# DigitalStylophone.net
KiCad netlist of a schematic drawn in EAGLE
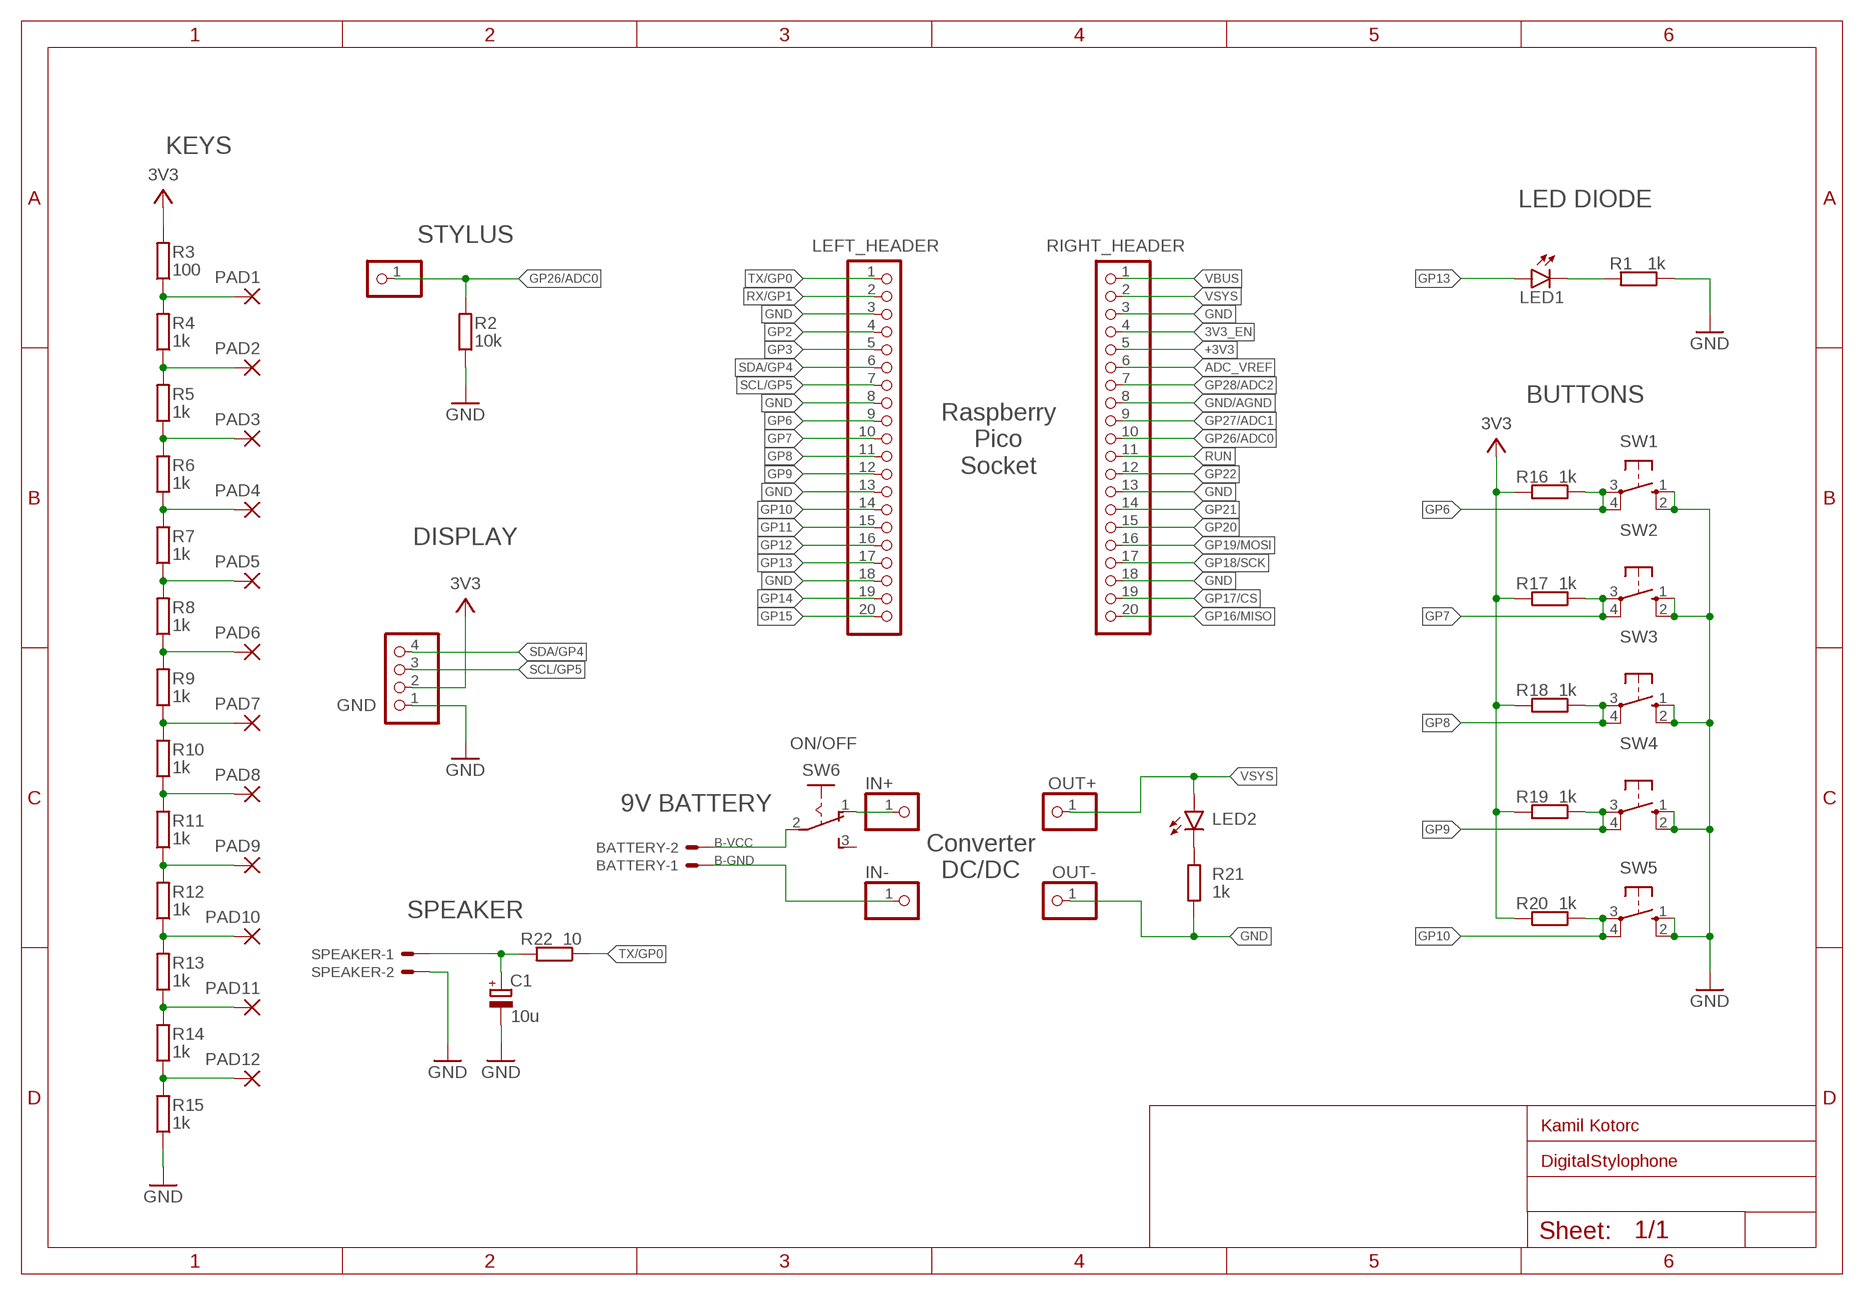
[diagram p0: schematic, sheet 1]

(export (version "E")
  (design (tool "Eeschema 10.0.6"))
  (components
    (comp (ref "BATTERY")
      (value "9V BATTERY")
      (footprint "eagle-import:22-23-2021")
      (fields (field (name "MF") "MOLEX") (field (name "MPN") "22-23-2021"))
      (libsource (lib "eagle-import") (part "22-23-2021"))
    )
    (comp (ref "C1")
      (value "10u")
      (footprint "eagle-import:E2,5-5")
      (libsource (lib "eagle-import") (part "CPOL-EUE2.5-5"))
    )
    (comp (ref "DISPLAY")
      (value "GND")
      (footprint "eagle-import:1X04")
      (libsource (lib "eagle-import") (part "PINHD-1X4"))
    )
    (comp (ref "IN+")
      (value "PINHD-1X1")
      (footprint "eagle-import:1X01")
      (libsource (lib "eagle-import") (part "PINHD-1X1"))
    )
    (comp (ref "IN-")
      (value "PINHD-1X1")
      (footprint "eagle-import:1X01")
      (libsource (lib "eagle-import") (part "PINHD-1X1"))
    )
    (comp (ref "LED1")
      (value "LED5MM")
      (footprint "eagle-import:LED5MM")
      (libsource (lib "eagle-import") (part "LED5MM"))
    )
    (comp (ref "LED2")
      (value "LED3MM")
      (footprint "eagle-import:LED3MM")
      (libsource (lib "eagle-import") (part "LED3MM"))
    )
    (comp (ref "LEFT_HEADER")
      (value "PINHD-1X20")
      (footprint "eagle-import:1X20")
      (libsource (lib "eagle-import") (part "PINHD-1X20"))
    )
    (comp (ref "OUT+")
      (value "PINHD-1X1")
      (footprint "eagle-import:1X01")
      (libsource (lib "eagle-import") (part "PINHD-1X1"))
    )
    (comp (ref "OUT-")
      (value "PINHD-1X1")
      (footprint "eagle-import:1X01")
      (libsource (lib "eagle-import") (part "PINHD-1X1"))
    )
    (comp (ref "PAD1")
      (value "SMD5")
      (footprint "eagle-import:SMD2,54-5,08")
      (libsource (lib "eagle-import") (part "SMD5"))
    )
    (comp (ref "PAD2")
      (value "SMD5")
      (footprint "eagle-import:SMD2,54-5,08")
      (libsource (lib "eagle-import") (part "SMD5"))
    )
    (comp (ref "PAD3")
      (value "SMD5")
      (footprint "eagle-import:SMD2,54-5,08")
      (libsource (lib "eagle-import") (part "SMD5"))
    )
    (comp (ref "PAD4")
      (value "SMD5")
      (footprint "eagle-import:SMD2,54-5,08")
      (libsource (lib "eagle-import") (part "SMD5"))
    )
    (comp (ref "PAD5")
      (value "SMD5")
      (footprint "eagle-import:SMD2,54-5,08")
      (libsource (lib "eagle-import") (part "SMD5"))
    )
    (comp (ref "PAD6")
      (value "SMD5")
      (footprint "eagle-import:SMD2,54-5,08")
      (libsource (lib "eagle-import") (part "SMD5"))
    )
    (comp (ref "PAD7")
      (value "SMD5")
      (footprint "eagle-import:SMD2,54-5,08")
      (libsource (lib "eagle-import") (part "SMD5"))
    )
    (comp (ref "PAD8")
      (value "SMD5")
      (footprint "eagle-import:SMD2,54-5,08")
      (libsource (lib "eagle-import") (part "SMD5"))
    )
    (comp (ref "PAD9")
      (value "SMD5")
      (footprint "eagle-import:SMD2,54-5,08")
      (libsource (lib "eagle-import") (part "SMD5"))
    )
    (comp (ref "PAD10")
      (value "SMD5")
      (footprint "eagle-import:SMD2,54-5,08")
      (libsource (lib "eagle-import") (part "SMD5"))
    )
    (comp (ref "PAD11")
      (value "SMD5")
      (footprint "eagle-import:SMD2,54-5,08")
      (libsource (lib "eagle-import") (part "SMD5"))
    )
    (comp (ref "PAD12")
      (value "SMD5")
      (footprint "eagle-import:SMD2,54-5,08")
      (libsource (lib "eagle-import") (part "SMD5"))
    )
    (comp (ref "R1")
      (value "1k")
      (footprint "eagle-import:0204_7")
      (libsource (lib "eagle-import") (part "R-EU_0204/7"))
    )
    (comp (ref "R2")
      (value "10k")
      (footprint "eagle-import:0204_7")
      (libsource (lib "eagle-import") (part "R-EU_0204/7"))
    )
    (comp (ref "R3")
      (value "100")
      (footprint "eagle-import:0204_7")
      (libsource (lib "eagle-import") (part "R-EU_0204/7"))
    )
    (comp (ref "R4")
      (value "1k")
      (footprint "eagle-import:0204_7")
      (libsource (lib "eagle-import") (part "R-EU_0204/7"))
    )
    (comp (ref "R5")
      (value "1k")
      (footprint "eagle-import:0204_7")
      (libsource (lib "eagle-import") (part "R-EU_0204/7"))
    )
    (comp (ref "R6")
      (value "1k")
      (footprint "eagle-import:0204_7")
      (libsource (lib "eagle-import") (part "R-EU_0204/7"))
    )
    (comp (ref "R7")
      (value "1k")
      (footprint "eagle-import:0204_7")
      (libsource (lib "eagle-import") (part "R-EU_0204/7"))
    )
    (comp (ref "R8")
      (value "1k")
      (footprint "eagle-import:0204_7")
      (libsource (lib "eagle-import") (part "R-EU_0204/7"))
    )
    (comp (ref "R9")
      (value "1k")
      (footprint "eagle-import:0204_7")
      (libsource (lib "eagle-import") (part "R-EU_0204/7"))
    )
    (comp (ref "R10")
      (value "1k")
      (footprint "eagle-import:0204_7")
      (libsource (lib "eagle-import") (part "R-EU_0204/7"))
    )
    (comp (ref "R11")
      (value "1k")
      (footprint "eagle-import:0204_7")
      (libsource (lib "eagle-import") (part "R-EU_0204/7"))
    )
    (comp (ref "R12")
      (value "1k")
      (footprint "eagle-import:0204_7")
      (libsource (lib "eagle-import") (part "R-EU_0204/7"))
    )
    (comp (ref "R13")
      (value "1k")
      (footprint "eagle-import:0204_7")
      (libsource (lib "eagle-import") (part "R-EU_0204/7"))
    )
    (comp (ref "R14")
      (value "1k")
      (footprint "eagle-import:0204_7")
      (libsource (lib "eagle-import") (part "R-EU_0204/7"))
    )
    (comp (ref "R15")
      (value "1k")
      (footprint "eagle-import:0204_7")
      (libsource (lib "eagle-import") (part "R-EU_0204/7"))
    )
    (comp (ref "R16")
      (value "1k")
      (footprint "eagle-import:0204_7")
      (libsource (lib "eagle-import") (part "R-EU_0204/7"))
    )
    (comp (ref "R17")
      (value "1k")
      (footprint "eagle-import:0204_7")
      (libsource (lib "eagle-import") (part "R-EU_0204/7"))
    )
    (comp (ref "R18")
      (value "1k")
      (footprint "eagle-import:0204_7")
      (libsource (lib "eagle-import") (part "R-EU_0204/7"))
    )
    (comp (ref "R19")
      (value "1k")
      (footprint "eagle-import:0204_7")
      (libsource (lib "eagle-import") (part "R-EU_0204/7"))
    )
    (comp (ref "R20")
      (value "1k")
      (footprint "eagle-import:0204_7")
      (libsource (lib "eagle-import") (part "R-EU_0204/7"))
    )
    (comp (ref "R21")
      (value "1k")
      (footprint "eagle-import:0204_7")
      (libsource (lib "eagle-import") (part "R-EU_0204/7"))
    )
    (comp (ref "R22")
      (value "10")
      (footprint "eagle-import:0204_7")
      (libsource (lib "eagle-import") (part "R-EU_0204/7"))
    )
    (comp (ref "RIGHT_HEADER")
      (value "PINHD-1X20")
      (footprint "eagle-import:1X20")
      (libsource (lib "eagle-import") (part "PINHD-1X20"))
    )
    (comp (ref "SPEAKER")
      (value "SPEAKER")
      (footprint "eagle-import:22-23-2021")
      (fields (field (name "MF") "MOLEX") (field (name "MPN") "22-23-2021"))
      (libsource (lib "eagle-import") (part "22-23-2021"))
    )
    (comp (ref "STYLUS")
      (value "PINHD-1X1")
      (footprint "eagle-import:1X01")
      (libsource (lib "eagle-import") (part "PINHD-1X1"))
    )
    (comp (ref "SW1")
      (value "10-XX")
      (footprint "eagle-import:B3F-10XX")
      (fields (field (name "MPN") "B3F-1000"))
      (libsource (lib "eagle-import") (part "10-XX"))
    )
    (comp (ref "SW2")
      (value "10-XX")
      (footprint "eagle-import:B3F-10XX")
      (fields (field (name "MPN") "B3F-1000"))
      (libsource (lib "eagle-import") (part "10-XX"))
    )
    (comp (ref "SW3")
      (value "10-XX")
      (footprint "eagle-import:B3F-10XX")
      (fields (field (name "MPN") "B3F-1000"))
      (libsource (lib "eagle-import") (part "10-XX"))
    )
    (comp (ref "SW4")
      (value "10-XX")
      (footprint "eagle-import:B3F-10XX")
      (fields (field (name "MPN") "B3F-1000"))
      (libsource (lib "eagle-import") (part "10-XX"))
    )
    (comp (ref "SW5")
      (value "10-XX")
      (footprint "eagle-import:B3F-10XX")
      (fields (field (name "MPN") "B3F-1000"))
      (libsource (lib "eagle-import") (part "10-XX"))
    )
    (comp (ref "SW6")
      (value "ON/OFF")
      (footprint "eagle-import:255SB")
      (libsource (lib "eagle-import") (part "255SB"))
    )
  )
  (nets
    (net (code "1") (name "+3V3") (class "Default")
      (node (ref "DISPLAY") (pin "2") (pinfunction "2_2") (pintype "passive"))
      (node (ref "R16") (pin "2") (pinfunction "2_2") (pintype "passive"))
      (node (ref "R17") (pin "2") (pinfunction "2_2") (pintype "passive"))
      (node (ref "R18") (pin "2") (pinfunction "2_2") (pintype "passive"))
      (node (ref "R19") (pin "2") (pinfunction "2_2") (pintype "passive"))
      (node (ref "R20") (pin "2") (pinfunction "2_2") (pintype "passive"))
      (node (ref "R3") (pin "2") (pinfunction "2_2") (pintype "passive"))
      (node (ref "RIGHT_HEADER") (pin "5") (pinfunction "5_5") (pintype "passive"))
    )
    (net (code "2") (name "/B-GND") (class "Default")
      (node (ref "BATTERY") (pin "1") (pinfunction "S_1") (pintype "passive"))
      (node (ref "IN-") (pin "1") (pinfunction "1_1") (pintype "passive"))
    )
    (net (code "3") (name "/B-VCC") (class "Default")
      (node (ref "BATTERY") (pin "2") (pinfunction "S_2") (pintype "passive"))
      (node (ref "SW6") (pin "2") (pinfunction "P_2") (pintype "passive"))
    )
    (net (code "4") (name "3V3_EN") (class "Default")
      (node (ref "RIGHT_HEADER") (pin "4") (pinfunction "4_4") (pintype "passive"))
    )
    (net (code "5") (name "ADC_VREF") (class "Default")
      (node (ref "RIGHT_HEADER") (pin "6") (pinfunction "6_6") (pintype "passive"))
    )
    (net (code "6") (name "GND") (class "Default")
      (node (ref "C1") (pin "-") (pinfunction "-_-") (pintype "passive"))
      (node (ref "DISPLAY") (pin "1") (pinfunction "1_1") (pintype "passive"))
      (node (ref "LEFT_HEADER") (pin "13") (pinfunction "13_13") (pintype "passive"))
      (node (ref "LEFT_HEADER") (pin "18") (pinfunction "18_18") (pintype "passive"))
      (node (ref "LEFT_HEADER") (pin "3") (pinfunction "3_3") (pintype "passive"))
      (node (ref "LEFT_HEADER") (pin "8") (pinfunction "8_8") (pintype "passive"))
      (node (ref "OUT-") (pin "1") (pinfunction "1_1") (pintype "passive"))
      (node (ref "R1") (pin "1") (pinfunction "1_1") (pintype "passive"))
      (node (ref "R15") (pin "1") (pinfunction "1_1") (pintype "passive"))
      (node (ref "R2") (pin "1") (pinfunction "1_1") (pintype "passive"))
      (node (ref "R21") (pin "1") (pinfunction "1_1") (pintype "passive"))
      (node (ref "RIGHT_HEADER") (pin "13") (pinfunction "13_13") (pintype "passive"))
      (node (ref "RIGHT_HEADER") (pin "18") (pinfunction "18_18") (pintype "passive"))
      (node (ref "RIGHT_HEADER") (pin "3") (pinfunction "3_3") (pintype "passive"))
      (node (ref "SPEAKER") (pin "2") (pinfunction "S_2") (pintype "passive"))
      (node (ref "SW1") (pin "1") (pinfunction "S_1") (pintype "passive"))
      (node (ref "SW1") (pin "2") (pinfunction "S1_2") (pintype "passive"))
      (node (ref "SW2") (pin "1") (pinfunction "S_1") (pintype "passive"))
      (node (ref "SW2") (pin "2") (pinfunction "S1_2") (pintype "passive"))
      (node (ref "SW3") (pin "1") (pinfunction "S_1") (pintype "passive"))
      (node (ref "SW3") (pin "2") (pinfunction "S1_2") (pintype "passive"))
      (node (ref "SW4") (pin "1") (pinfunction "S_1") (pintype "passive"))
      (node (ref "SW4") (pin "2") (pinfunction "S1_2") (pintype "passive"))
      (node (ref "SW5") (pin "1") (pinfunction "S_1") (pintype "passive"))
      (node (ref "SW5") (pin "2") (pinfunction "S1_2") (pintype "passive"))
    )
    (net (code "7") (name "GND{slash}AGND") (class "Default")
      (node (ref "RIGHT_HEADER") (pin "8") (pinfunction "8_8") (pintype "passive"))
    )
    (net (code "8") (name "GP2") (class "Default")
      (node (ref "LEFT_HEADER") (pin "4") (pinfunction "4_4") (pintype "passive"))
    )
    (net (code "9") (name "GP3") (class "Default")
      (node (ref "LEFT_HEADER") (pin "5") (pinfunction "5_5") (pintype "passive"))
    )
    (net (code "10") (name "GP6") (class "Default")
      (node (ref "LEFT_HEADER") (pin "9") (pinfunction "9_9") (pintype "passive"))
      (node (ref "R16") (pin "1") (pinfunction "1_1") (pintype "passive"))
      (node (ref "SW1") (pin "3") (pinfunction "P_3") (pintype "passive"))
      (node (ref "SW1") (pin "4") (pinfunction "P1_4") (pintype "passive"))
    )
    (net (code "11") (name "GP7") (class "Default")
      (node (ref "LEFT_HEADER") (pin "10") (pinfunction "10_10") (pintype "passive"))
      (node (ref "R17") (pin "1") (pinfunction "1_1") (pintype "passive"))
      (node (ref "SW2") (pin "3") (pinfunction "P_3") (pintype "passive"))
      (node (ref "SW2") (pin "4") (pinfunction "P1_4") (pintype "passive"))
    )
    (net (code "12") (name "GP8") (class "Default")
      (node (ref "LEFT_HEADER") (pin "11") (pinfunction "11_11") (pintype "passive"))
      (node (ref "R18") (pin "1") (pinfunction "1_1") (pintype "passive"))
      (node (ref "SW3") (pin "3") (pinfunction "P_3") (pintype "passive"))
      (node (ref "SW3") (pin "4") (pinfunction "P1_4") (pintype "passive"))
    )
    (net (code "13") (name "GP9") (class "Default")
      (node (ref "LEFT_HEADER") (pin "12") (pinfunction "12_12") (pintype "passive"))
      (node (ref "R19") (pin "1") (pinfunction "1_1") (pintype "passive"))
      (node (ref "SW4") (pin "3") (pinfunction "P_3") (pintype "passive"))
      (node (ref "SW4") (pin "4") (pinfunction "P1_4") (pintype "passive"))
    )
    (net (code "14") (name "GP10") (class "Default")
      (node (ref "LEFT_HEADER") (pin "14") (pinfunction "14_14") (pintype "passive"))
      (node (ref "R20") (pin "1") (pinfunction "1_1") (pintype "passive"))
      (node (ref "SW5") (pin "3") (pinfunction "P_3") (pintype "passive"))
      (node (ref "SW5") (pin "4") (pinfunction "P1_4") (pintype "passive"))
    )
    (net (code "15") (name "GP11") (class "Default")
      (node (ref "LEFT_HEADER") (pin "15") (pinfunction "15_15") (pintype "passive"))
    )
    (net (code "16") (name "GP12") (class "Default")
      (node (ref "LEFT_HEADER") (pin "16") (pinfunction "16_16") (pintype "passive"))
    )
    (net (code "17") (name "GP13") (class "Default")
      (node (ref "LED1") (pin "A") (pinfunction "A_A") (pintype "passive"))
      (node (ref "LEFT_HEADER") (pin "17") (pinfunction "17_17") (pintype "passive"))
    )
    (net (code "18") (name "GP14") (class "Default")
      (node (ref "LEFT_HEADER") (pin "19") (pinfunction "19_19") (pintype "passive"))
    )
    (net (code "19") (name "GP15") (class "Default")
      (node (ref "LEFT_HEADER") (pin "20") (pinfunction "20_20") (pintype "passive"))
    )
    (net (code "20") (name "GP16{slash}MISO") (class "Default")
      (node (ref "RIGHT_HEADER") (pin "20") (pinfunction "20_20") (pintype "passive"))
    )
    (net (code "21") (name "GP17{slash}CS") (class "Default")
      (node (ref "RIGHT_HEADER") (pin "19") (pinfunction "19_19") (pintype "passive"))
    )
    (net (code "22") (name "GP18{slash}SCK") (class "Default")
      (node (ref "RIGHT_HEADER") (pin "17") (pinfunction "17_17") (pintype "passive"))
    )
    (net (code "23") (name "GP19{slash}MOSI") (class "Default")
      (node (ref "RIGHT_HEADER") (pin "16") (pinfunction "16_16") (pintype "passive"))
    )
    (net (code "24") (name "GP20") (class "Default")
      (node (ref "RIGHT_HEADER") (pin "15") (pinfunction "15_15") (pintype "passive"))
    )
    (net (code "25") (name "GP21") (class "Default")
      (node (ref "RIGHT_HEADER") (pin "14") (pinfunction "14_14") (pintype "passive"))
    )
    (net (code "26") (name "GP22") (class "Default")
      (node (ref "RIGHT_HEADER") (pin "12") (pinfunction "12_12") (pintype "passive"))
    )
    (net (code "27") (name "GP26{slash}ADC0") (class "Default")
      (node (ref "R2") (pin "2") (pinfunction "2_2") (pintype "passive"))
      (node (ref "RIGHT_HEADER") (pin "10") (pinfunction "10_10") (pintype "passive"))
      (node (ref "STYLUS") (pin "1") (pinfunction "1_1") (pintype "passive"))
    )
    (net (code "28") (name "GP27{slash}ADC1") (class "Default")
      (node (ref "RIGHT_HEADER") (pin "9") (pinfunction "9_9") (pintype "passive"))
    )
    (net (code "29") (name "GP28{slash}ADC2") (class "Default")
      (node (ref "RIGHT_HEADER") (pin "7") (pinfunction "7_7") (pintype "passive"))
    )
    (net (code "30") (name "Net-(LED1-C)") (class "Default")
      (node (ref "LED1") (pin "K") (pinfunction "C_K") (pintype "passive"))
      (node (ref "R1") (pin "2") (pinfunction "2_2") (pintype "passive"))
    )
    (net (code "31") (name "Net-(LED2-C)") (class "Default")
      (node (ref "LED2") (pin "K") (pinfunction "C_K") (pintype "passive"))
      (node (ref "R21") (pin "2") (pinfunction "2_2") (pintype "passive"))
    )
    (net (code "32") (name "Net-(PAD1-P)") (class "Default")
      (node (ref "PAD1") (pin "1") (pinfunction "P_1") (pintype "passive"))
      (node (ref "R3") (pin "1") (pinfunction "1_1") (pintype "passive"))
      (node (ref "R4") (pin "2") (pinfunction "2_2") (pintype "passive"))
    )
    (net (code "33") (name "Net-(PAD2-P)") (class "Default")
      (node (ref "PAD2") (pin "1") (pinfunction "P_1") (pintype "passive"))
      (node (ref "R4") (pin "1") (pinfunction "1_1") (pintype "passive"))
      (node (ref "R5") (pin "2") (pinfunction "2_2") (pintype "passive"))
    )
    (net (code "34") (name "Net-(PAD3-P)") (class "Default")
      (node (ref "PAD3") (pin "1") (pinfunction "P_1") (pintype "passive"))
      (node (ref "R5") (pin "1") (pinfunction "1_1") (pintype "passive"))
      (node (ref "R6") (pin "2") (pinfunction "2_2") (pintype "passive"))
    )
    (net (code "35") (name "Net-(PAD4-P)") (class "Default")
      (node (ref "PAD4") (pin "1") (pinfunction "P_1") (pintype "passive"))
      (node (ref "R6") (pin "1") (pinfunction "1_1") (pintype "passive"))
      (node (ref "R7") (pin "2") (pinfunction "2_2") (pintype "passive"))
    )
    (net (code "36") (name "Net-(PAD5-P)") (class "Default")
      (node (ref "PAD5") (pin "1") (pinfunction "P_1") (pintype "passive"))
      (node (ref "R7") (pin "1") (pinfunction "1_1") (pintype "passive"))
      (node (ref "R8") (pin "2") (pinfunction "2_2") (pintype "passive"))
    )
    (net (code "37") (name "Net-(PAD6-P)") (class "Default")
      (node (ref "PAD6") (pin "1") (pinfunction "P_1") (pintype "passive"))
      (node (ref "R8") (pin "1") (pinfunction "1_1") (pintype "passive"))
      (node (ref "R9") (pin "2") (pinfunction "2_2") (pintype "passive"))
    )
    (net (code "38") (name "Net-(PAD7-P)") (class "Default")
      (node (ref "PAD7") (pin "1") (pinfunction "P_1") (pintype "passive"))
      (node (ref "R10") (pin "2") (pinfunction "2_2") (pintype "passive"))
      (node (ref "R9") (pin "1") (pinfunction "1_1") (pintype "passive"))
    )
    (net (code "39") (name "Net-(PAD8-P)") (class "Default")
      (node (ref "PAD8") (pin "1") (pinfunction "P_1") (pintype "passive"))
      (node (ref "R10") (pin "1") (pinfunction "1_1") (pintype "passive"))
      (node (ref "R11") (pin "2") (pinfunction "2_2") (pintype "passive"))
    )
    (net (code "40") (name "Net-(PAD9-P)") (class "Default")
      (node (ref "PAD9") (pin "1") (pinfunction "P_1") (pintype "passive"))
      (node (ref "R11") (pin "1") (pinfunction "1_1") (pintype "passive"))
      (node (ref "R12") (pin "2") (pinfunction "2_2") (pintype "passive"))
    )
    (net (code "41") (name "Net-(PAD10-P)") (class "Default")
      (node (ref "PAD10") (pin "1") (pinfunction "P_1") (pintype "passive"))
      (node (ref "R12") (pin "1") (pinfunction "1_1") (pintype "passive"))
      (node (ref "R13") (pin "2") (pinfunction "2_2") (pintype "passive"))
    )
    (net (code "42") (name "Net-(PAD11-P)") (class "Default")
      (node (ref "PAD11") (pin "1") (pinfunction "P_1") (pintype "passive"))
      (node (ref "R13") (pin "1") (pinfunction "1_1") (pintype "passive"))
      (node (ref "R14") (pin "2") (pinfunction "2_2") (pintype "passive"))
    )
    (net (code "43") (name "Net-(PAD12-P)") (class "Default")
      (node (ref "PAD12") (pin "1") (pinfunction "P_1") (pintype "passive"))
      (node (ref "R14") (pin "1") (pinfunction "1_1") (pintype "passive"))
      (node (ref "R15") (pin "2") (pinfunction "2_2") (pintype "passive"))
    )
    (net (code "44") (name "Net-(SPEAKERA-S)") (class "Default")
      (node (ref "C1") (pin "+") (pinfunction "+_+") (pintype "passive"))
      (node (ref "R22") (pin "2") (pinfunction "2_2") (pintype "passive"))
      (node (ref "SPEAKER") (pin "1") (pinfunction "S_1") (pintype "passive"))
    )
    (net (code "45") (name "Net-(SW6-O)") (class "Default")
      (node (ref "IN+") (pin "1") (pinfunction "1_1") (pintype "passive"))
      (node (ref "SW6") (pin "1") (pinfunction "O_1") (pintype "passive"))
    )
    (net (code "46") (name "RUN") (class "Default")
      (node (ref "RIGHT_HEADER") (pin "11") (pinfunction "11_11") (pintype "passive"))
    )
    (net (code "47") (name "RX{slash}GP1") (class "Default")
      (node (ref "LEFT_HEADER") (pin "2") (pinfunction "2_2") (pintype "passive"))
    )
    (net (code "48") (name "SCL{slash}GP5") (class "Default")
      (node (ref "DISPLAY") (pin "3") (pinfunction "3_3") (pintype "passive"))
      (node (ref "LEFT_HEADER") (pin "7") (pinfunction "7_7") (pintype "passive"))
    )
    (net (code "49") (name "SDA{slash}GP4") (class "Default")
      (node (ref "DISPLAY") (pin "4") (pinfunction "4_4") (pintype "passive"))
      (node (ref "LEFT_HEADER") (pin "6") (pinfunction "6_6") (pintype "passive"))
    )
    (net (code "50") (name "TX{slash}GP0") (class "Default")
      (node (ref "LEFT_HEADER") (pin "1") (pinfunction "1_1") (pintype "passive"))
      (node (ref "R22") (pin "1") (pinfunction "1_1") (pintype "passive"))
    )
    (net (code "51") (name "VBUS") (class "Default")
      (node (ref "RIGHT_HEADER") (pin "1") (pinfunction "1_1") (pintype "passive"))
    )
    (net (code "52") (name "VSYS") (class "Default")
      (node (ref "LED2") (pin "A") (pinfunction "A_A") (pintype "passive"))
      (node (ref "OUT+") (pin "1") (pinfunction "1_1") (pintype "passive"))
      (node (ref "RIGHT_HEADER") (pin "2") (pinfunction "2_2") (pintype "passive"))
    )
    (net (code "53") (name "unconnected-(SW6-S-Pad3)") (class "Default")
      (node (ref "SW6") (pin "3") (pinfunction "S_3") (pintype "passive"))
    )
  )
)
